# otternet_v2a_cc1101.net
KiCad netlist of a schematic drawn in EAGLE
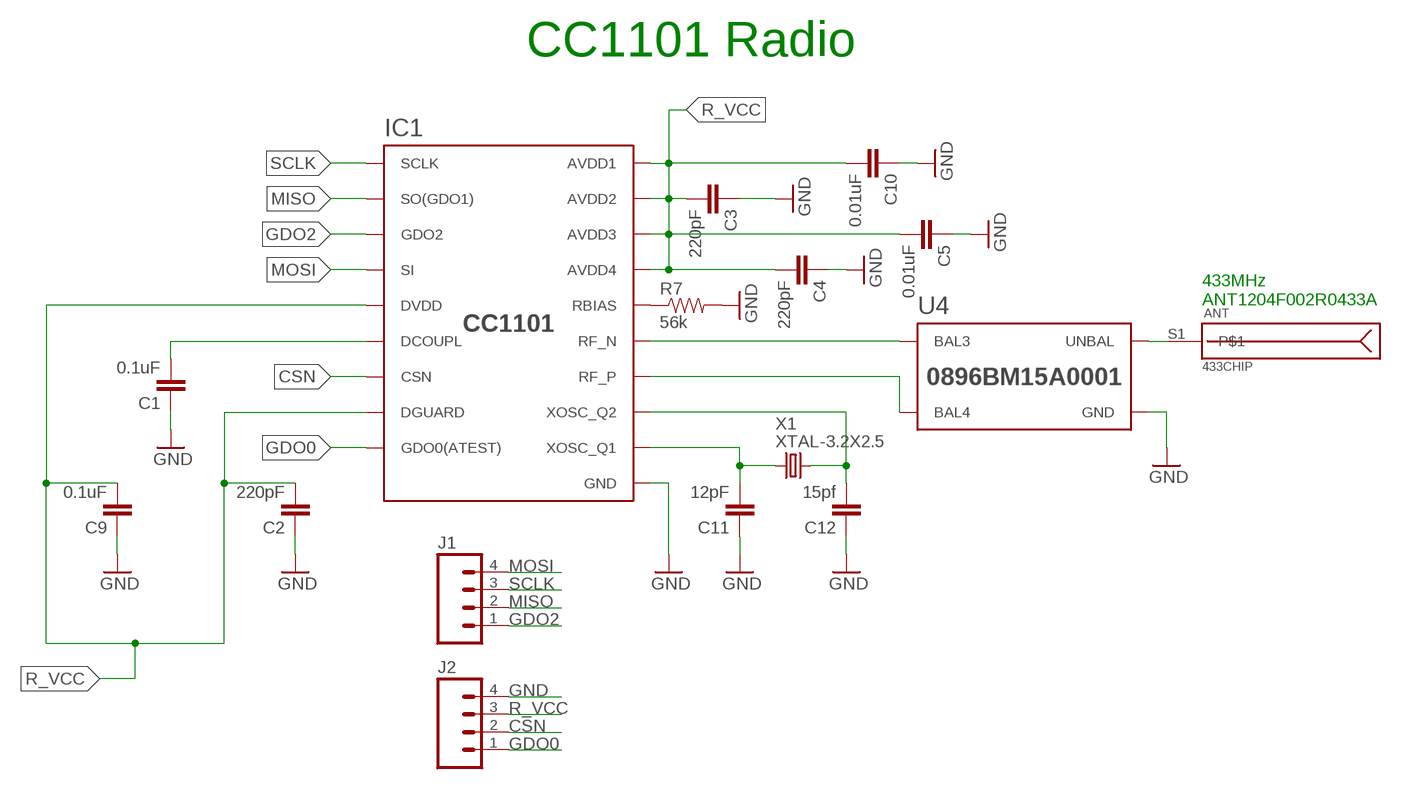
[diagram p0: schematic, sheet 1]

(export (version "E")
  (design (tool "Eeschema 10.0.6"))
  (components
    (comp (ref "ANT")
      (value "433CHIP")
      (footprint "eagle-import:ANT-433-USP")
      (libsource (lib "eagle-import") (part "433CHIP"))
    )
    (comp (ref "C1")
      (value "0.1uF")
      (footprint "eagle-import:0402")
      (libsource (lib "eagle-import") (part "C-EU"))
    )
    (comp (ref "C2")
      (value "220pF")
      (footprint "eagle-import:0402")
      (libsource (lib "eagle-import") (part "C-EU"))
    )
    (comp (ref "C3")
      (value "220pF")
      (footprint "eagle-import:0402")
      (libsource (lib "eagle-import") (part "C-EU"))
    )
    (comp (ref "C4")
      (value "220pF")
      (footprint "eagle-import:0402")
      (libsource (lib "eagle-import") (part "C-EU"))
    )
    (comp (ref "C5")
      (value "0.01uF")
      (footprint "eagle-import:0402")
      (libsource (lib "eagle-import") (part "C-EU"))
    )
    (comp (ref "C9")
      (value "0.1uF")
      (footprint "eagle-import:0402")
      (libsource (lib "eagle-import") (part "C-EU"))
    )
    (comp (ref "C10")
      (value "0.01uF")
      (footprint "eagle-import:0402")
      (libsource (lib "eagle-import") (part "C-EU"))
    )
    (comp (ref "C11")
      (value "12pF")
      (footprint "eagle-import:0402")
      (libsource (lib "eagle-import") (part "C-EU"))
    )
    (comp (ref "C12")
      (value "15pf")
      (footprint "eagle-import:0402")
      (libsource (lib "eagle-import") (part "C-EU"))
    )
    (comp (ref "IC1")
      (value "CC1101")
      (footprint "eagle-import:QLP20")
      (libsource (lib "eagle-import") (part "CC1101"))
    )
    (comp (ref "J1")
      (value "M04PTH")
      (footprint "eagle-import:1X04")
      (libsource (lib "eagle-import") (part "M04PTH"))
    )
    (comp (ref "J2")
      (value "M04PTH")
      (footprint "eagle-import:1X04")
      (libsource (lib "eagle-import") (part "M04PTH"))
    )
    (comp (ref "R7")
      (value "56k")
      (footprint "eagle-import:0402")
      (libsource (lib "eagle-import") (part "R-EU"))
    )
    (comp (ref "U4")
      (value "0896BM15A0001")
      (footprint "eagle-import:XXXXBM15A0001")
      (libsource (lib "eagle-import") (part "0896BM15A0001"))
    )
    (comp (ref "X1")
      (value "XTAL-3.2X2.5")
      (footprint "eagle-import:XTAL-3.2X2.5")
      (libsource (lib "eagle-import") (part "XTAL-3.2X2.5"))
    )
  )
  (nets
    (net (code "1") (name "CSN") (class "Default")
      (node (ref "IC1") (pin "7") (pinfunction "CSN_7") (pintype "bidirectional"))
      (node (ref "J2") (pin "2") (pinfunction "2_2") (pintype "passive"))
    )
    (net (code "2") (name "GDO0") (class "Default")
      (node (ref "IC1") (pin "6") (pinfunction "GDO0(ATEST)_6") (pintype "bidirectional"))
      (node (ref "J2") (pin "1") (pinfunction "1_1") (pintype "passive"))
    )
    (net (code "3") (name "GDO2") (class "Default")
      (node (ref "IC1") (pin "3") (pinfunction "GDO2_3") (pintype "bidirectional"))
      (node (ref "J1") (pin "1") (pinfunction "1_1") (pintype "passive"))
    )
    (net (code "4") (name "GND") (class "Default")
      (node (ref "C1") (pin "1") (pinfunction "1_1") (pintype "passive"))
      (node (ref "C10") (pin "1") (pinfunction "1_1") (pintype "passive"))
      (node (ref "C11") (pin "1") (pinfunction "1_1") (pintype "passive"))
      (node (ref "C12") (pin "1") (pinfunction "1_1") (pintype "passive"))
      (node (ref "C2") (pin "1") (pinfunction "1_1") (pintype "passive"))
      (node (ref "C3") (pin "1") (pinfunction "1_1") (pintype "passive"))
      (node (ref "C4") (pin "1") (pinfunction "1_1") (pintype "passive"))
      (node (ref "C5") (pin "1") (pinfunction "1_1") (pintype "passive"))
      (node (ref "C9") (pin "1") (pinfunction "1_1") (pintype "passive"))
      (node (ref "IC1") (pin "16") (pinfunction "GND_16") (pintype "bidirectional"))
      (node (ref "IC1") (pin "19") (pinfunction "GND_19") (pintype "bidirectional"))
      (node (ref "IC1") (pin "GND") (pinfunction "GND_GND") (pintype "bidirectional"))
      (node (ref "IC1") (pin "GND1") (pinfunction "GND_GND1") (pintype "bidirectional"))
      (node (ref "IC1") (pin "GND2") (pinfunction "GND_GND2") (pintype "bidirectional"))
      (node (ref "IC1") (pin "GND3") (pinfunction "GND_GND3") (pintype "bidirectional"))
      (node (ref "IC1") (pin "GND4") (pinfunction "GND_GND4") (pintype "bidirectional"))
      (node (ref "IC1") (pin "GND5") (pinfunction "GND_GND5") (pintype "bidirectional"))
      (node (ref "J2") (pin "4") (pinfunction "4_4") (pintype "passive"))
      (node (ref "R7") (pin "2") (pinfunction "2_2") (pintype "passive"))
      (node (ref "U4") (pin "2") (pinfunction "GND_2") (pintype "bidirectional"))
      (node (ref "U4") (pin "5") (pinfunction "GND_5") (pintype "bidirectional"))
      (node (ref "U4") (pin "6") (pinfunction "GND_6") (pintype "bidirectional"))
    )
    (net (code "5") (name "MISO") (class "Default")
      (node (ref "IC1") (pin "2") (pinfunction "SO(GDO1)_2") (pintype "bidirectional"))
      (node (ref "J1") (pin "2") (pinfunction "2_2") (pintype "passive"))
    )
    (net (code "6") (name "MOSI") (class "Default")
      (node (ref "IC1") (pin "20") (pinfunction "SI_20") (pintype "bidirectional"))
      (node (ref "J1") (pin "4") (pinfunction "4_4") (pintype "passive"))
    )
    (net (code "7") (name "Net-(ANT-P$1)") (class "Default")
      (node (ref "ANT") (pin "S1") (pinfunction "P$1_S1") (pintype "bidirectional"))
      (node (ref "U4") (pin "1") (pinfunction "UNBAL_1") (pintype "bidirectional"))
    )
    (net (code "8") (name "Net-(IC1-DCOUPL)") (class "Default")
      (node (ref "C1") (pin "2") (pinfunction "2_2") (pintype "passive"))
      (node (ref "IC1") (pin "5") (pinfunction "DCOUPL_5") (pintype "bidirectional"))
    )
    (net (code "9") (name "Net-(IC1-RBIAS)") (class "Default")
      (node (ref "IC1") (pin "17") (pinfunction "RBIAS_17") (pintype "bidirectional"))
      (node (ref "R7") (pin "1") (pinfunction "1_1") (pintype "passive"))
    )
    (net (code "10") (name "Net-(IC1-RF_N)") (class "Default")
      (node (ref "IC1") (pin "13") (pinfunction "RF_N_13") (pintype "bidirectional"))
      (node (ref "U4") (pin "3") (pinfunction "BAL3_3") (pintype "bidirectional"))
    )
    (net (code "11") (name "Net-(IC1-RF_P)") (class "Default")
      (node (ref "IC1") (pin "12") (pinfunction "RF_P_12") (pintype "bidirectional"))
      (node (ref "U4") (pin "4") (pinfunction "BAL4_4") (pintype "bidirectional"))
    )
    (net (code "12") (name "Net-(IC1-XOSC_Q1)") (class "Default")
      (node (ref "C11") (pin "2") (pinfunction "2_2") (pintype "passive"))
      (node (ref "IC1") (pin "8") (pinfunction "XOSC_Q1_8") (pintype "bidirectional"))
      (node (ref "X1") (pin "1") (pinfunction "1_1") (pintype "passive"))
    )
    (net (code "13") (name "Net-(IC1-XOSC_Q2)") (class "Default")
      (node (ref "C12") (pin "2") (pinfunction "2_2") (pintype "passive"))
      (node (ref "IC1") (pin "10") (pinfunction "XOSC_Q2_10") (pintype "bidirectional"))
      (node (ref "X1") (pin "3") (pinfunction "2_3") (pintype "passive"))
    )
    (net (code "14") (name "R_VCC") (class "Default")
      (node (ref "C10") (pin "2") (pinfunction "2_2") (pintype "passive"))
      (node (ref "C2") (pin "2") (pinfunction "2_2") (pintype "passive"))
      (node (ref "C3") (pin "2") (pinfunction "2_2") (pintype "passive"))
      (node (ref "C4") (pin "2") (pinfunction "2_2") (pintype "passive"))
      (node (ref "C5") (pin "2") (pinfunction "2_2") (pintype "passive"))
      (node (ref "C9") (pin "2") (pinfunction "2_2") (pintype "passive"))
      (node (ref "IC1") (pin "11") (pinfunction "AVDD2_11") (pintype "bidirectional"))
      (node (ref "IC1") (pin "14") (pinfunction "AVDD3_14") (pintype "bidirectional"))
      (node (ref "IC1") (pin "15") (pinfunction "AVDD4_15") (pintype "bidirectional"))
      (node (ref "IC1") (pin "18") (pinfunction "DGUARD_18") (pintype "bidirectional"))
      (node (ref "IC1") (pin "4") (pinfunction "DVDD_4") (pintype "bidirectional"))
      (node (ref "IC1") (pin "9") (pinfunction "AVDD1_9") (pintype "bidirectional"))
      (node (ref "J2") (pin "3") (pinfunction "3_3") (pintype "passive"))
    )
    (net (code "15") (name "SCLK") (class "Default")
      (node (ref "IC1") (pin "1") (pinfunction "SCLK_1") (pintype "bidirectional"))
      (node (ref "J1") (pin "3") (pinfunction "3_3") (pintype "passive"))
    )
  )
)
